# Epaper_bob.net
KiCad netlist of a schematic drawn in EAGLE
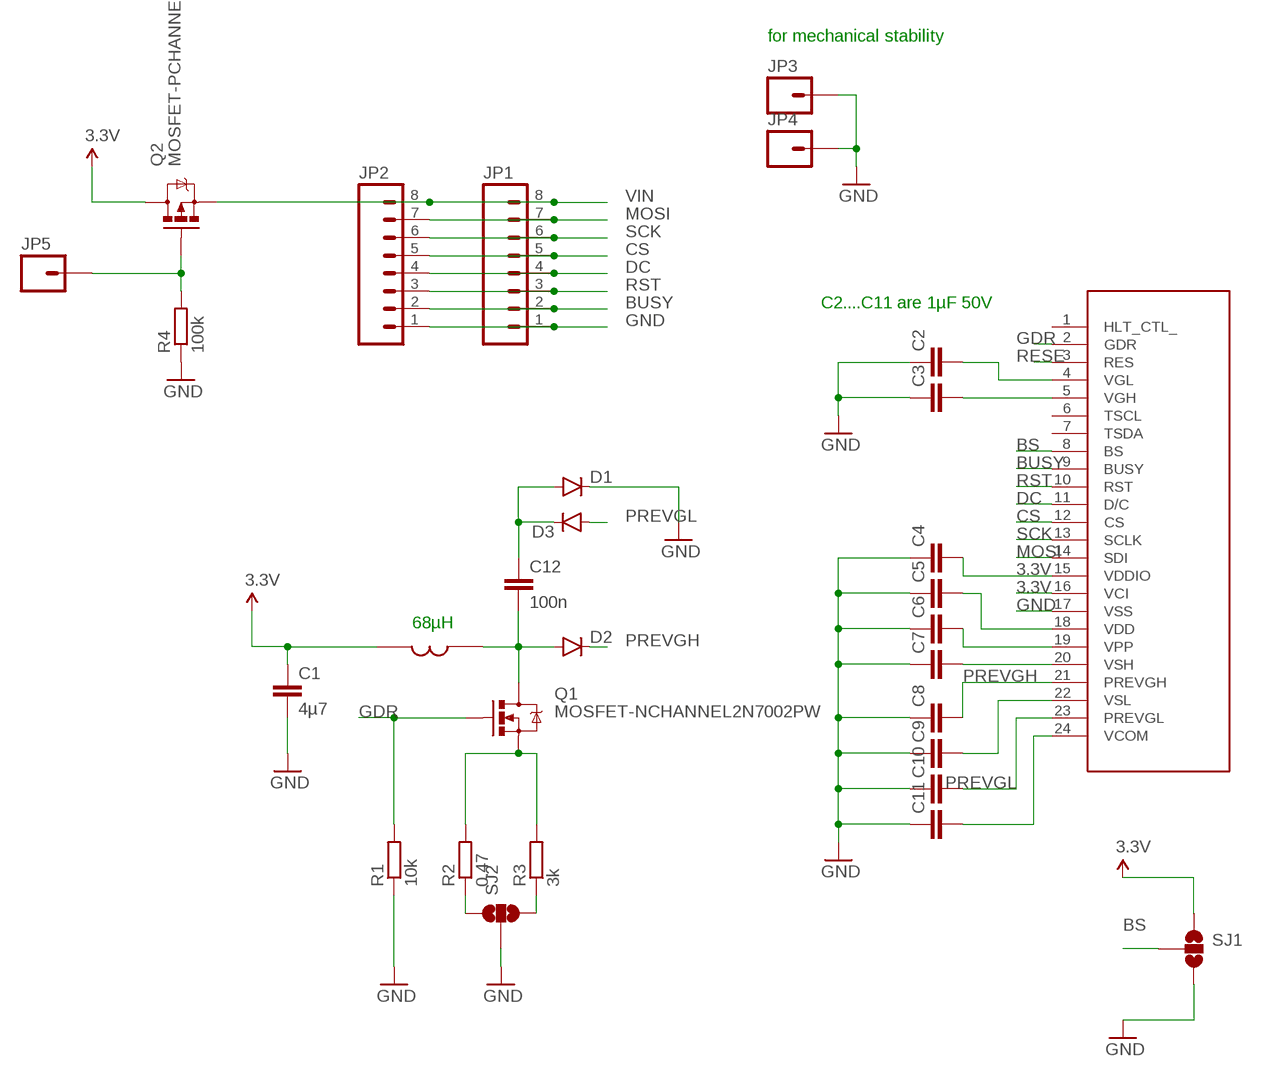
[diagram p0: schematic, sheet 1]

(export (version "E")
  (design (tool "Eeschema 10.0.6"))
  (components
    (comp (ref "C1")
      (value "4µ7")
      (footprint "eagle-import:C0603")
      (libsource (lib "eagle-import") (part "C-EUC0603"))
    )
    (comp (ref "C2")
      (value "C-EUC0603")
      (footprint "eagle-import:C0603")
      (libsource (lib "eagle-import") (part "C-EUC0603"))
    )
    (comp (ref "C3")
      (value "C-EUC0603")
      (footprint "eagle-import:C0603")
      (libsource (lib "eagle-import") (part "C-EUC0603"))
    )
    (comp (ref "C4")
      (value "C-EUC0603")
      (footprint "eagle-import:C0603")
      (libsource (lib "eagle-import") (part "C-EUC0603"))
    )
    (comp (ref "C5")
      (value "C-EUC0603")
      (footprint "eagle-import:C0603")
      (libsource (lib "eagle-import") (part "C-EUC0603"))
    )
    (comp (ref "C6")
      (value "C-EUC0603")
      (footprint "eagle-import:C0603")
      (libsource (lib "eagle-import") (part "C-EUC0603"))
    )
    (comp (ref "C7")
      (value "C-EUC0603")
      (footprint "eagle-import:C0603")
      (libsource (lib "eagle-import") (part "C-EUC0603"))
    )
    (comp (ref "C8")
      (value "C-EUC0603")
      (footprint "eagle-import:C0603")
      (libsource (lib "eagle-import") (part "C-EUC0603"))
    )
    (comp (ref "C9")
      (value "C-EUC0603")
      (footprint "eagle-import:C0603")
      (libsource (lib "eagle-import") (part "C-EUC0603"))
    )
    (comp (ref "C10")
      (value "C-EUC0603")
      (footprint "eagle-import:C0603")
      (libsource (lib "eagle-import") (part "C-EUC0603"))
    )
    (comp (ref "C11")
      (value "C-EUC0603")
      (footprint "eagle-import:C0603")
      (libsource (lib "eagle-import") (part "C-EUC0603"))
    )
    (comp (ref "C12")
      (value "100n")
      (footprint "eagle-import:C0603")
      (libsource (lib "eagle-import") (part "C-EUC0603"))
    )
    (comp (ref "D1")
      (value "DIODESOD123")
      (footprint "eagle-import:SOD-123")
      (libsource (lib "eagle-import") (part "DIODESOD123"))
    )
    (comp (ref "D2")
      (value "DIODESOD123")
      (footprint "eagle-import:SOD-123")
      (libsource (lib "eagle-import") (part "DIODESOD123"))
    )
    (comp (ref "D3")
      (value "DIODESOD123")
      (footprint "eagle-import:SOD-123")
      (libsource (lib "eagle-import") (part "DIODESOD123"))
    )
    (comp (ref "JP1")
      (value "M08NO_SILK")
      (footprint "eagle-import:1X08_PIN1_NO_SILK")
      (libsource (lib "eagle-import") (part "M08NO_SILK"))
    )
    (comp (ref "JP2")
      (value "M08")
      (footprint "eagle-import:1X08_ROUND")
      (libsource (lib "eagle-import") (part "M08"))
    )
    (comp (ref "JP3")
      (value "M01PTH_NO_SILK_YES_STOP")
      (footprint "eagle-import:1X01_NO_SILK")
      (libsource (lib "eagle-import") (part "M01PTH_NO_SILK_YES_STOP"))
    )
    (comp (ref "JP4")
      (value "M01PTH_NO_SILK_YES_STOP")
      (footprint "eagle-import:1X01_NO_SILK")
      (libsource (lib "eagle-import") (part "M01PTH_NO_SILK_YES_STOP"))
    )
    (comp (ref "JP5")
      (value "M01PTH_NO_SILK_YES_STOP")
      (footprint "eagle-import:1X01_NO_SILK")
      (libsource (lib "eagle-import") (part "M01PTH_NO_SILK_YES_STOP"))
    )
    (comp (ref "Q1")
      (value "MOSFET-NCHANNEL2N7002PW")
      (footprint "eagle-import:SOT323")
      (libsource (lib "eagle-import") (part "MOSFET-NCHANNEL2N7002PW"))
    )
    (comp (ref "Q2")
      (value "MOSFET-PCHANNEL")
      (footprint "eagle-import:SOT23-3")
      (libsource (lib "eagle-import") (part "MOSFET-PCHANNEL"))
    )
    (comp (ref "R1")
      (value "10k")
      (footprint "eagle-import:R0603")
      (libsource (lib "eagle-import") (part "R-EU_R0603"))
    )
    (comp (ref "R2")
      (value "0.47")
      (footprint "eagle-import:R0603")
      (libsource (lib "eagle-import") (part "R-EU_R0603"))
    )
    (comp (ref "R3")
      (value "3k")
      (footprint "eagle-import:R0603")
      (libsource (lib "eagle-import") (part "R-EU_R0603"))
    )
    (comp (ref "R4")
      (value "100k")
      (footprint "eagle-import:R0603")
      (libsource (lib "eagle-import") (part "R-EU_R0603"))
    )
    (comp (ref "SJ1")
      (value "SOLDERJUMPER_2WAYS")
      (footprint "eagle-import:SJ_3")
      (libsource (lib "eagle-import") (part "SOLDERJUMPER_2WAYS"))
    )
    (comp (ref "SJ2")
      (value "SOLDERJUMPER_2WAYS")
      (footprint "eagle-import:SJ_3")
      (libsource (lib "eagle-import") (part "SOLDERJUMPER_2WAYS"))
    )
    (comp (ref "U$1")
      (value "E-PAPER")
      (footprint "eagle-import:FPC24")
      (libsource (lib "eagle-import") (part "E-PAPER"))
    )
    (comp (ref "U$2")
      (value "LQH3_INDUCTOR")
      (footprint "eagle-import:LQH3_INDUCTOR")
      (libsource (lib "eagle-import") (part "LQH3_INDUCTOR"))
    )
  )
  (nets
    (net (code "1") (name "/BS") (class "Default")
      (node (ref "SJ1") (pin "2") (pinfunction "2_2") (pintype "passive"))
      (node (ref "U$1") (pin "8") (pinfunction "BS_8") (pintype "bidirectional"))
    )
    (net (code "2") (name "/BUSY") (class "Default")
      (node (ref "JP1") (pin "2") (pinfunction "2_2") (pintype "passive"))
      (node (ref "JP2") (pin "2") (pinfunction "2_2") (pintype "passive"))
      (node (ref "U$1") (pin "9") (pinfunction "BUSY_9") (pintype "bidirectional"))
    )
    (net (code "3") (name "/CS") (class "Default")
      (node (ref "JP1") (pin "5") (pinfunction "5_5") (pintype "passive"))
      (node (ref "JP2") (pin "5") (pinfunction "5_5") (pintype "passive"))
      (node (ref "U$1") (pin "12") (pinfunction "CS_12") (pintype "bidirectional"))
    )
    (net (code "4") (name "/DC") (class "Default")
      (node (ref "JP1") (pin "4") (pinfunction "4_4") (pintype "passive"))
      (node (ref "JP2") (pin "4") (pinfunction "4_4") (pintype "passive"))
      (node (ref "U$1") (pin "11") (pinfunction "D/C_11") (pintype "bidirectional"))
    )
    (net (code "5") (name "/GDR") (class "Default")
      (node (ref "Q1") (pin "1") (pinfunction "G_1") (pintype "passive"))
      (node (ref "R1") (pin "2") (pinfunction "2_2") (pintype "passive"))
      (node (ref "U$1") (pin "2") (pinfunction "GDR_2") (pintype "bidirectional"))
    )
    (net (code "6") (name "/MOSI") (class "Default")
      (node (ref "JP1") (pin "7") (pinfunction "7_7") (pintype "passive"))
      (node (ref "JP2") (pin "7") (pinfunction "7_7") (pintype "passive"))
      (node (ref "U$1") (pin "14") (pinfunction "SDI_14") (pintype "bidirectional"))
    )
    (net (code "7") (name "/PREVGH") (class "Default")
      (node (ref "C8") (pin "2") (pinfunction "2_2") (pintype "passive"))
      (node (ref "D2") (pin "C") (pinfunction "C_C") (pintype "passive"))
      (node (ref "U$1") (pin "21") (pinfunction "PREVGH_21") (pintype "bidirectional"))
    )
    (net (code "8") (name "/PREVGL") (class "Default")
      (node (ref "C10") (pin "2") (pinfunction "2_2") (pintype "passive"))
      (node (ref "D3") (pin "A") (pinfunction "A_A") (pintype "passive"))
      (node (ref "U$1") (pin "23") (pinfunction "PREVGL_23") (pintype "bidirectional"))
    )
    (net (code "9") (name "/RESE") (class "Default")
      (node (ref "U$1") (pin "3") (pinfunction "RES_3") (pintype "bidirectional"))
    )
    (net (code "10") (name "/RST") (class "Default")
      (node (ref "JP1") (pin "3") (pinfunction "3_3") (pintype "passive"))
      (node (ref "JP2") (pin "3") (pinfunction "3_3") (pintype "passive"))
      (node (ref "U$1") (pin "10") (pinfunction "RST_10") (pintype "bidirectional"))
    )
    (net (code "11") (name "/SCK") (class "Default")
      (node (ref "JP1") (pin "6") (pinfunction "6_6") (pintype "passive"))
      (node (ref "JP2") (pin "6") (pinfunction "6_6") (pintype "passive"))
      (node (ref "U$1") (pin "13") (pinfunction "SCLK_13") (pintype "bidirectional"))
    )
    (net (code "12") (name "/VIN") (class "Default")
      (node (ref "JP1") (pin "8") (pinfunction "8_8") (pintype "passive"))
      (node (ref "JP2") (pin "8") (pinfunction "8_8") (pintype "passive"))
      (node (ref "Q2") (pin "2") (pinfunction "S_2") (pintype "passive"))
    )
    (net (code "13") (name "3.3V") (class "Default")
      (node (ref "C1") (pin "1") (pinfunction "1_1") (pintype "passive"))
      (node (ref "C4") (pin "2") (pinfunction "2_2") (pintype "passive"))
      (node (ref "Q2") (pin "3") (pinfunction "D_3") (pintype "passive"))
      (node (ref "SJ1") (pin "1") (pinfunction "1_1") (pintype "passive"))
      (node (ref "U$1") (pin "15") (pinfunction "VDDIO_15") (pintype "bidirectional"))
      (node (ref "U$1") (pin "16") (pinfunction "VCI_16") (pintype "bidirectional"))
      (node (ref "U$2") (pin "P$1") (pinfunction "2_P$1") (pintype "bidirectional"))
    )
    (net (code "14") (name "GND") (class "Default")
      (node (ref "C1") (pin "2") (pinfunction "2_2") (pintype "passive"))
      (node (ref "C10") (pin "1") (pinfunction "1_1") (pintype "passive"))
      (node (ref "C11") (pin "1") (pinfunction "1_1") (pintype "passive"))
      (node (ref "C2") (pin "1") (pinfunction "1_1") (pintype "passive"))
      (node (ref "C3") (pin "1") (pinfunction "1_1") (pintype "passive"))
      (node (ref "C4") (pin "1") (pinfunction "1_1") (pintype "passive"))
      (node (ref "C5") (pin "1") (pinfunction "1_1") (pintype "passive"))
      (node (ref "C6") (pin "1") (pinfunction "1_1") (pintype "passive"))
      (node (ref "C7") (pin "1") (pinfunction "1_1") (pintype "passive"))
      (node (ref "C8") (pin "1") (pinfunction "1_1") (pintype "passive"))
      (node (ref "C9") (pin "1") (pinfunction "1_1") (pintype "passive"))
      (node (ref "D1") (pin "C") (pinfunction "C_C") (pintype "passive"))
      (node (ref "JP1") (pin "1") (pinfunction "1_1") (pintype "passive"))
      (node (ref "JP2") (pin "1") (pinfunction "1_1") (pintype "passive"))
      (node (ref "JP3") (pin "1") (pinfunction "1_1") (pintype "passive"))
      (node (ref "JP4") (pin "1") (pinfunction "1_1") (pintype "passive"))
      (node (ref "R1") (pin "1") (pinfunction "1_1") (pintype "passive"))
      (node (ref "R4") (pin "1") (pinfunction "1_1") (pintype "passive"))
      (node (ref "SJ1") (pin "3") (pinfunction "3_3") (pintype "passive"))
      (node (ref "SJ2") (pin "2") (pinfunction "2_2") (pintype "passive"))
      (node (ref "U$1") (pin "17") (pinfunction "VSS_17") (pintype "bidirectional"))
    )
    (net (code "15") (name "Net-(C12-Pad1)") (class "Default")
      (node (ref "C12") (pin "1") (pinfunction "1_1") (pintype "passive"))
      (node (ref "D1") (pin "A") (pinfunction "A_A") (pintype "passive"))
      (node (ref "D3") (pin "C") (pinfunction "C_C") (pintype "passive"))
    )
    (net (code "16") (name "Net-(Q1-D)") (class "Default")
      (node (ref "C12") (pin "2") (pinfunction "2_2") (pintype "passive"))
      (node (ref "D2") (pin "A") (pinfunction "A_A") (pintype "passive"))
      (node (ref "Q1") (pin "3") (pinfunction "D_3") (pintype "passive"))
      (node (ref "U$2") (pin "P$2") (pinfunction "P$2_P$2") (pintype "bidirectional"))
    )
    (net (code "17") (name "Net-(Q1-S)") (class "Default")
      (node (ref "Q1") (pin "2") (pinfunction "S_2") (pintype "passive"))
      (node (ref "R2") (pin "2") (pinfunction "2_2") (pintype "passive"))
      (node (ref "R3") (pin "2") (pinfunction "2_2") (pintype "passive"))
    )
    (net (code "18") (name "Net-(Q2-G)") (class "Default")
      (node (ref "JP5") (pin "1") (pinfunction "1_1") (pintype "passive"))
      (node (ref "Q2") (pin "1") (pinfunction "G_1") (pintype "passive"))
      (node (ref "R4") (pin "2") (pinfunction "2_2") (pintype "passive"))
    )
    (net (code "19") (name "Net-(R2-Pad1)") (class "Default")
      (node (ref "R2") (pin "1") (pinfunction "1_1") (pintype "passive"))
      (node (ref "SJ2") (pin "1") (pinfunction "1_1") (pintype "passive"))
    )
    (net (code "20") (name "Net-(R3-Pad1)") (class "Default")
      (node (ref "R3") (pin "1") (pinfunction "1_1") (pintype "passive"))
      (node (ref "SJ2") (pin "3") (pinfunction "3_3") (pintype "passive"))
    )
    (net (code "21") (name "Net-(U$1-VCOM)") (class "Default")
      (node (ref "C11") (pin "2") (pinfunction "2_2") (pintype "passive"))
      (node (ref "U$1") (pin "24") (pinfunction "VCOM_24") (pintype "bidirectional"))
    )
    (net (code "22") (name "Net-(U$1-VDD)") (class "Default")
      (node (ref "C5") (pin "2") (pinfunction "2_2") (pintype "passive"))
      (node (ref "U$1") (pin "18") (pinfunction "VDD_18") (pintype "bidirectional"))
    )
    (net (code "23") (name "Net-(U$1-VGH)") (class "Default")
      (node (ref "C3") (pin "2") (pinfunction "2_2") (pintype "passive"))
      (node (ref "U$1") (pin "5") (pinfunction "VGH_5") (pintype "bidirectional"))
    )
    (net (code "24") (name "Net-(U$1-VGL)") (class "Default")
      (node (ref "C2") (pin "2") (pinfunction "2_2") (pintype "passive"))
      (node (ref "U$1") (pin "4") (pinfunction "VGL_4") (pintype "bidirectional"))
    )
    (net (code "25") (name "Net-(U$1-VPP)") (class "Default")
      (node (ref "C6") (pin "2") (pinfunction "2_2") (pintype "passive"))
      (node (ref "U$1") (pin "19") (pinfunction "VPP_19") (pintype "bidirectional"))
    )
    (net (code "26") (name "Net-(U$1-VSH)") (class "Default")
      (node (ref "C7") (pin "2") (pinfunction "2_2") (pintype "passive"))
      (node (ref "U$1") (pin "20") (pinfunction "VSH_20") (pintype "bidirectional"))
    )
    (net (code "27") (name "Net-(U$1-VSL)") (class "Default")
      (node (ref "C9") (pin "2") (pinfunction "2_2") (pintype "passive"))
      (node (ref "U$1") (pin "22") (pinfunction "VSL_22") (pintype "bidirectional"))
    )
    (net (code "28") (name "unconnected-(U$1-HLT_CTL_-Pad1)") (class "Default")
      (node (ref "U$1") (pin "1") (pinfunction "HLT_CTL__1") (pintype "bidirectional"))
    )
    (net (code "29") (name "unconnected-(U$1-TSCL-Pad6)") (class "Default")
      (node (ref "U$1") (pin "6") (pinfunction "TSCL_6") (pintype "bidirectional"))
    )
    (net (code "30") (name "unconnected-(U$1-TSDA-Pad7)") (class "Default")
      (node (ref "U$1") (pin "7") (pinfunction "TSDA_7") (pintype "bidirectional"))
    )
  )
)
